# 4440.net
KiCad netlist of a schematic drawn in EAGLE
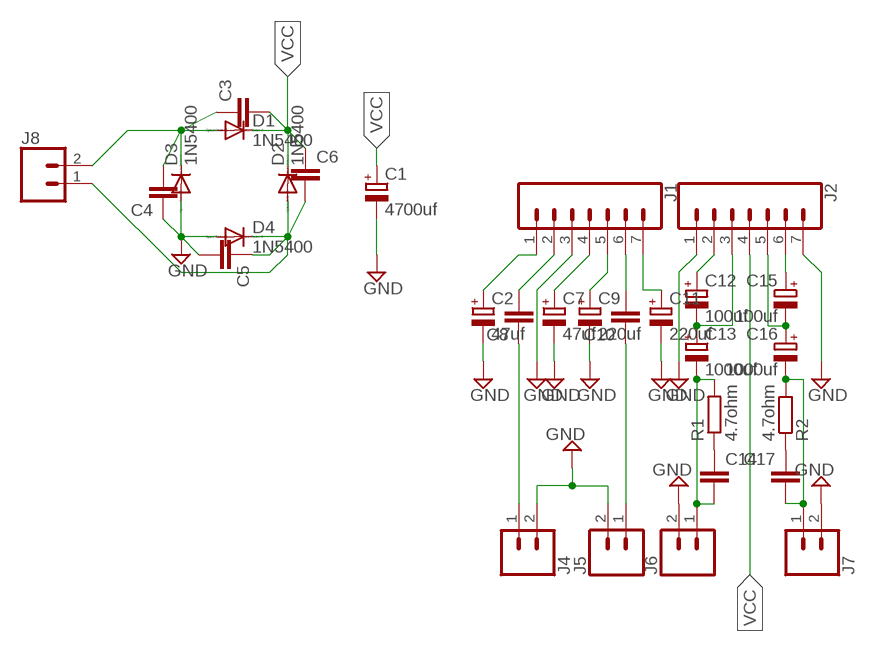
[diagram p0: schematic, sheet 1]

(export (version "E")
  (design (tool "Eeschema 10.0.6"))
  (components
    (comp (ref "C1")
      (value "4700uf")
      (footprint "eagle-import:E7,5-16")
      (libsource (lib "eagle-import") (part "CPOL-EUE7.5-16"))
    )
    (comp (ref "C2")
      (value "47uf")
      (footprint "eagle-import:E3,5-8")
      (libsource (lib "eagle-import") (part "CPOL-EUE3.5-8"))
    )
    (comp (ref "C3")
      (value "C-EU050-055X075")
      (footprint "eagle-import:C050-055X075")
      (libsource (lib "eagle-import") (part "C-EU050-055X075"))
    )
    (comp (ref "C4")
      (value "C-EU050-055X075")
      (footprint "eagle-import:C050-055X075")
      (libsource (lib "eagle-import") (part "C-EU050-055X075"))
    )
    (comp (ref "C5")
      (value "C-EU050-055X075")
      (footprint "eagle-import:C050-055X075")
      (libsource (lib "eagle-import") (part "C-EU050-055X075"))
    )
    (comp (ref "C6")
      (value "C-EU050-055X075")
      (footprint "eagle-import:C050-055X075")
      (libsource (lib "eagle-import") (part "C-EU050-055X075"))
    )
    (comp (ref "C7")
      (value "47uf")
      (footprint "eagle-import:E3,5-8")
      (libsource (lib "eagle-import") (part "CPOL-EUE3.5-8"))
    )
    (comp (ref "C8")
      (value "C-EU050-055X075")
      (footprint "eagle-import:C050-055X075")
      (libsource (lib "eagle-import") (part "C-EU050-055X075"))
    )
    (comp (ref "C9")
      (value "220uf")
      (footprint "eagle-import:E3,5-8")
      (libsource (lib "eagle-import") (part "CPOL-EUE3.5-8"))
    )
    (comp (ref "C10")
      (value "C-EU050-055X075")
      (footprint "eagle-import:C050-055X075")
      (libsource (lib "eagle-import") (part "C-EU050-055X075"))
    )
    (comp (ref "C11")
      (value "220uf")
      (footprint "eagle-import:E3,5-8")
      (libsource (lib "eagle-import") (part "CPOL-EUE3.5-8"))
    )
    (comp (ref "C12")
      (value "100uf")
      (footprint "eagle-import:E3,5-8")
      (libsource (lib "eagle-import") (part "CPOL-EUE3.5-8"))
    )
    (comp (ref "C13")
      (value "1000uf")
      (footprint "eagle-import:E7,5-16")
      (libsource (lib "eagle-import") (part "CPOL-EUE7.5-16"))
    )
    (comp (ref "C14")
      (value "C-EU050-055X075")
      (footprint "eagle-import:C050-055X075")
      (libsource (lib "eagle-import") (part "C-EU050-055X075"))
    )
    (comp (ref "C15")
      (value "100uf")
      (footprint "eagle-import:E3,5-8")
      (libsource (lib "eagle-import") (part "CPOL-EUE3.5-8"))
    )
    (comp (ref "C16")
      (value "1000uf")
      (footprint "eagle-import:E7,5-16")
      (libsource (lib "eagle-import") (part "CPOL-EUE7.5-16"))
    )
    (comp (ref "C17")
      (value "C-EU050-055X075")
      (footprint "eagle-import:C050-055X075")
      (libsource (lib "eagle-import") (part "C-EU050-055X075"))
    )
    (comp (ref "D1")
      (value "1N5400")
      (footprint "eagle-import:DO201-15")
      (libsource (lib "eagle-import") (part "1N5400"))
    )
    (comp (ref "D2")
      (value "1N5400")
      (footprint "eagle-import:DO201-15")
      (libsource (lib "eagle-import") (part "1N5400"))
    )
    (comp (ref "D3")
      (value "1N5400")
      (footprint "eagle-import:DO201-15")
      (libsource (lib "eagle-import") (part "1N5400"))
    )
    (comp (ref "D4")
      (value "1N5400")
      (footprint "eagle-import:DO201-15")
      (libsource (lib "eagle-import") (part "1N5400"))
    )
    (comp (ref "J1")
      (value "CONN_07LONGPADS")
      (footprint "eagle-import:1X07_LONGPADS")
      (libsource (lib "eagle-import") (part "CONN_07LONGPADS"))
    )
    (comp (ref "J2")
      (value "CONN_07LONGPADS")
      (footprint "eagle-import:1X07_LONGPADS")
      (libsource (lib "eagle-import") (part "CONN_07LONGPADS"))
    )
    (comp (ref "J4")
      (value "CONN_023.5MM-NO_SILK")
      (footprint "eagle-import:SCREWTERMINAL-3.5MM-2-NS")
      (libsource (lib "eagle-import") (part "CONN_023.5MM-NO_SILK"))
    )
    (comp (ref "J5")
      (value "CONN_023.5MM-NO_SILK")
      (footprint "eagle-import:SCREWTERMINAL-3.5MM-2-NS")
      (libsource (lib "eagle-import") (part "CONN_023.5MM-NO_SILK"))
    )
    (comp (ref "J6")
      (value "CONN_023.5MM-NO_SILK")
      (footprint "eagle-import:SCREWTERMINAL-3.5MM-2-NS")
      (libsource (lib "eagle-import") (part "CONN_023.5MM-NO_SILK"))
    )
    (comp (ref "J7")
      (value "CONN_023.5MM-NO_SILK")
      (footprint "eagle-import:SCREWTERMINAL-3.5MM-2-NS")
      (libsource (lib "eagle-import") (part "CONN_023.5MM-NO_SILK"))
    )
    (comp (ref "J8")
      (value "CONN_023.5MM-NO_SILK")
      (footprint "eagle-import:SCREWTERMINAL-3.5MM-2-NS")
      (libsource (lib "eagle-import") (part "CONN_023.5MM-NO_SILK"))
    )
    (comp (ref "R1")
      (value "4.7ohm")
      (footprint "eagle-import:0207_12")
      (libsource (lib "eagle-import") (part "R-EU_0207/12"))
    )
    (comp (ref "R2")
      (value "4.7ohm")
      (footprint "eagle-import:0207_12")
      (libsource (lib "eagle-import") (part "R-EU_0207/12"))
    )
  )
  (nets
    (net (code "1") (name "GND") (class "Default")
      (node (ref "C1") (pin "-") (pinfunction "-_-") (pintype "passive"))
      (node (ref "C11") (pin "-") (pinfunction "-_-") (pintype "passive"))
      (node (ref "C2") (pin "-") (pinfunction "-_-") (pintype "passive"))
      (node (ref "C4") (pin "1") (pinfunction "1_1") (pintype "passive"))
      (node (ref "C5") (pin "2") (pinfunction "2_2") (pintype "passive"))
      (node (ref "C7") (pin "-") (pinfunction "-_-") (pintype "passive"))
      (node (ref "C9") (pin "-") (pinfunction "-_-") (pintype "passive"))
      (node (ref "D3") (pin "A") (pinfunction "A_A") (pintype "passive"))
      (node (ref "D4") (pin "A") (pinfunction "A_A") (pintype "passive"))
      (node (ref "J1") (pin "3") (pinfunction "3_3") (pintype "passive"))
      (node (ref "J2") (pin "1") (pinfunction "1_1") (pintype "passive"))
      (node (ref "J2") (pin "7") (pinfunction "7_7") (pintype "passive"))
      (node (ref "J4") (pin "2") (pinfunction "2_2") (pintype "passive"))
      (node (ref "J5") (pin "2") (pinfunction "2_2") (pintype "passive"))
      (node (ref "J6") (pin "2") (pinfunction "2_2") (pintype "passive"))
      (node (ref "J7") (pin "2") (pinfunction "2_2") (pintype "passive"))
    )
    (net (code "2") (name "Net-(C2-Pad+)") (class "Default")
      (node (ref "C2") (pin "+") (pinfunction "+_+") (pintype "passive"))
      (node (ref "J1") (pin "1") (pinfunction "1_1") (pintype "passive"))
    )
    (net (code "3") (name "Net-(C3-Pad1)") (class "Default")
      (node (ref "C3") (pin "1") (pinfunction "1_1") (pintype "passive"))
      (node (ref "C4") (pin "2") (pinfunction "2_2") (pintype "passive"))
      (node (ref "D1") (pin "A") (pinfunction "A_A") (pintype "passive"))
      (node (ref "D3") (pin "C") (pinfunction "C_C") (pintype "passive"))
      (node (ref "J8") (pin "2") (pinfunction "2_2") (pintype "passive"))
    )
    (net (code "4") (name "Net-(C5-Pad1)") (class "Default")
      (node (ref "C5") (pin "1") (pinfunction "1_1") (pintype "passive"))
      (node (ref "C6") (pin "2") (pinfunction "2_2") (pintype "passive"))
      (node (ref "D2") (pin "A") (pinfunction "A_A") (pintype "passive"))
      (node (ref "D4") (pin "C") (pinfunction "C_C") (pintype "passive"))
      (node (ref "J8") (pin "1") (pinfunction "1_1") (pintype "passive"))
    )
    (net (code "5") (name "Net-(C7-Pad+)") (class "Default")
      (node (ref "C7") (pin "+") (pinfunction "+_+") (pintype "passive"))
      (node (ref "J1") (pin "4") (pinfunction "4_4") (pintype "passive"))
    )
    (net (code "6") (name "Net-(C8-Pad1)") (class "Default")
      (node (ref "C8") (pin "1") (pinfunction "1_1") (pintype "passive"))
      (node (ref "J4") (pin "1") (pinfunction "1_1") (pintype "passive"))
    )
    (net (code "7") (name "Net-(C8-Pad2)") (class "Default")
      (node (ref "C8") (pin "2") (pinfunction "2_2") (pintype "passive"))
      (node (ref "J1") (pin "2") (pinfunction "2_2") (pintype "passive"))
    )
    (net (code "8") (name "Net-(C9-Pad+)") (class "Default")
      (node (ref "C9") (pin "+") (pinfunction "+_+") (pintype "passive"))
      (node (ref "J1") (pin "5") (pinfunction "5_5") (pintype "passive"))
    )
    (net (code "9") (name "Net-(C10-Pad1)") (class "Default")
      (node (ref "C10") (pin "1") (pinfunction "1_1") (pintype "passive"))
      (node (ref "J5") (pin "1") (pinfunction "1_1") (pintype "passive"))
    )
    (net (code "10") (name "Net-(C10-Pad2)") (class "Default")
      (node (ref "C10") (pin "2") (pinfunction "2_2") (pintype "passive"))
      (node (ref "J1") (pin "6") (pinfunction "6_6") (pintype "passive"))
    )
    (net (code "11") (name "Net-(C11-Pad+)") (class "Default")
      (node (ref "C11") (pin "+") (pinfunction "+_+") (pintype "passive"))
      (node (ref "J1") (pin "7") (pinfunction "7_7") (pintype "passive"))
    )
    (net (code "12") (name "Net-(C12-Pad+)") (class "Default")
      (node (ref "C12") (pin "+") (pinfunction "+_+") (pintype "passive"))
      (node (ref "J2") (pin "2") (pinfunction "2_2") (pintype "passive"))
    )
    (net (code "13") (name "Net-(C12-Pad-)") (class "Default")
      (node (ref "C12") (pin "-") (pinfunction "-_-") (pintype "passive"))
      (node (ref "C13") (pin "+") (pinfunction "+_+") (pintype "passive"))
      (node (ref "J2") (pin "3") (pinfunction "3_3") (pintype "passive"))
    )
    (net (code "14") (name "Net-(C13-Pad-)") (class "Default")
      (node (ref "C13") (pin "-") (pinfunction "-_-") (pintype "passive"))
      (node (ref "C14") (pin "2") (pinfunction "2_2") (pintype "passive"))
      (node (ref "J6") (pin "1") (pinfunction "1_1") (pintype "passive"))
      (node (ref "R1") (pin "2") (pinfunction "2_2") (pintype "passive"))
    )
    (net (code "15") (name "Net-(C14-Pad1)") (class "Default")
      (node (ref "C14") (pin "1") (pinfunction "1_1") (pintype "passive"))
      (node (ref "R1") (pin "1") (pinfunction "1_1") (pintype "passive"))
    )
    (net (code "16") (name "Net-(C15-Pad+)") (class "Default")
      (node (ref "C15") (pin "+") (pinfunction "+_+") (pintype "passive"))
      (node (ref "J2") (pin "6") (pinfunction "6_6") (pintype "passive"))
    )
    (net (code "17") (name "Net-(C15-Pad-)") (class "Default")
      (node (ref "C15") (pin "-") (pinfunction "-_-") (pintype "passive"))
      (node (ref "C16") (pin "+") (pinfunction "+_+") (pintype "passive"))
      (node (ref "J2") (pin "5") (pinfunction "5_5") (pintype "passive"))
    )
    (net (code "18") (name "Net-(C16-Pad-)") (class "Default")
      (node (ref "C16") (pin "-") (pinfunction "-_-") (pintype "passive"))
      (node (ref "C17") (pin "2") (pinfunction "2_2") (pintype "passive"))
      (node (ref "J7") (pin "1") (pinfunction "1_1") (pintype "passive"))
      (node (ref "R2") (pin "2") (pinfunction "2_2") (pintype "passive"))
    )
    (net (code "19") (name "Net-(C17-Pad1)") (class "Default")
      (node (ref "C17") (pin "1") (pinfunction "1_1") (pintype "passive"))
      (node (ref "R2") (pin "1") (pinfunction "1_1") (pintype "passive"))
    )
    (net (code "20") (name "VCC") (class "Default")
      (node (ref "C1") (pin "+") (pinfunction "+_+") (pintype "passive"))
      (node (ref "C3") (pin "2") (pinfunction "2_2") (pintype "passive"))
      (node (ref "C6") (pin "1") (pinfunction "1_1") (pintype "passive"))
      (node (ref "D1") (pin "C") (pinfunction "C_C") (pintype "passive"))
      (node (ref "D2") (pin "C") (pinfunction "C_C") (pintype "passive"))
      (node (ref "J2") (pin "4") (pinfunction "4_4") (pintype "passive"))
    )
  )
)
